# Phase_3.net
KiCad netlist of a schematic drawn in Altium Designer
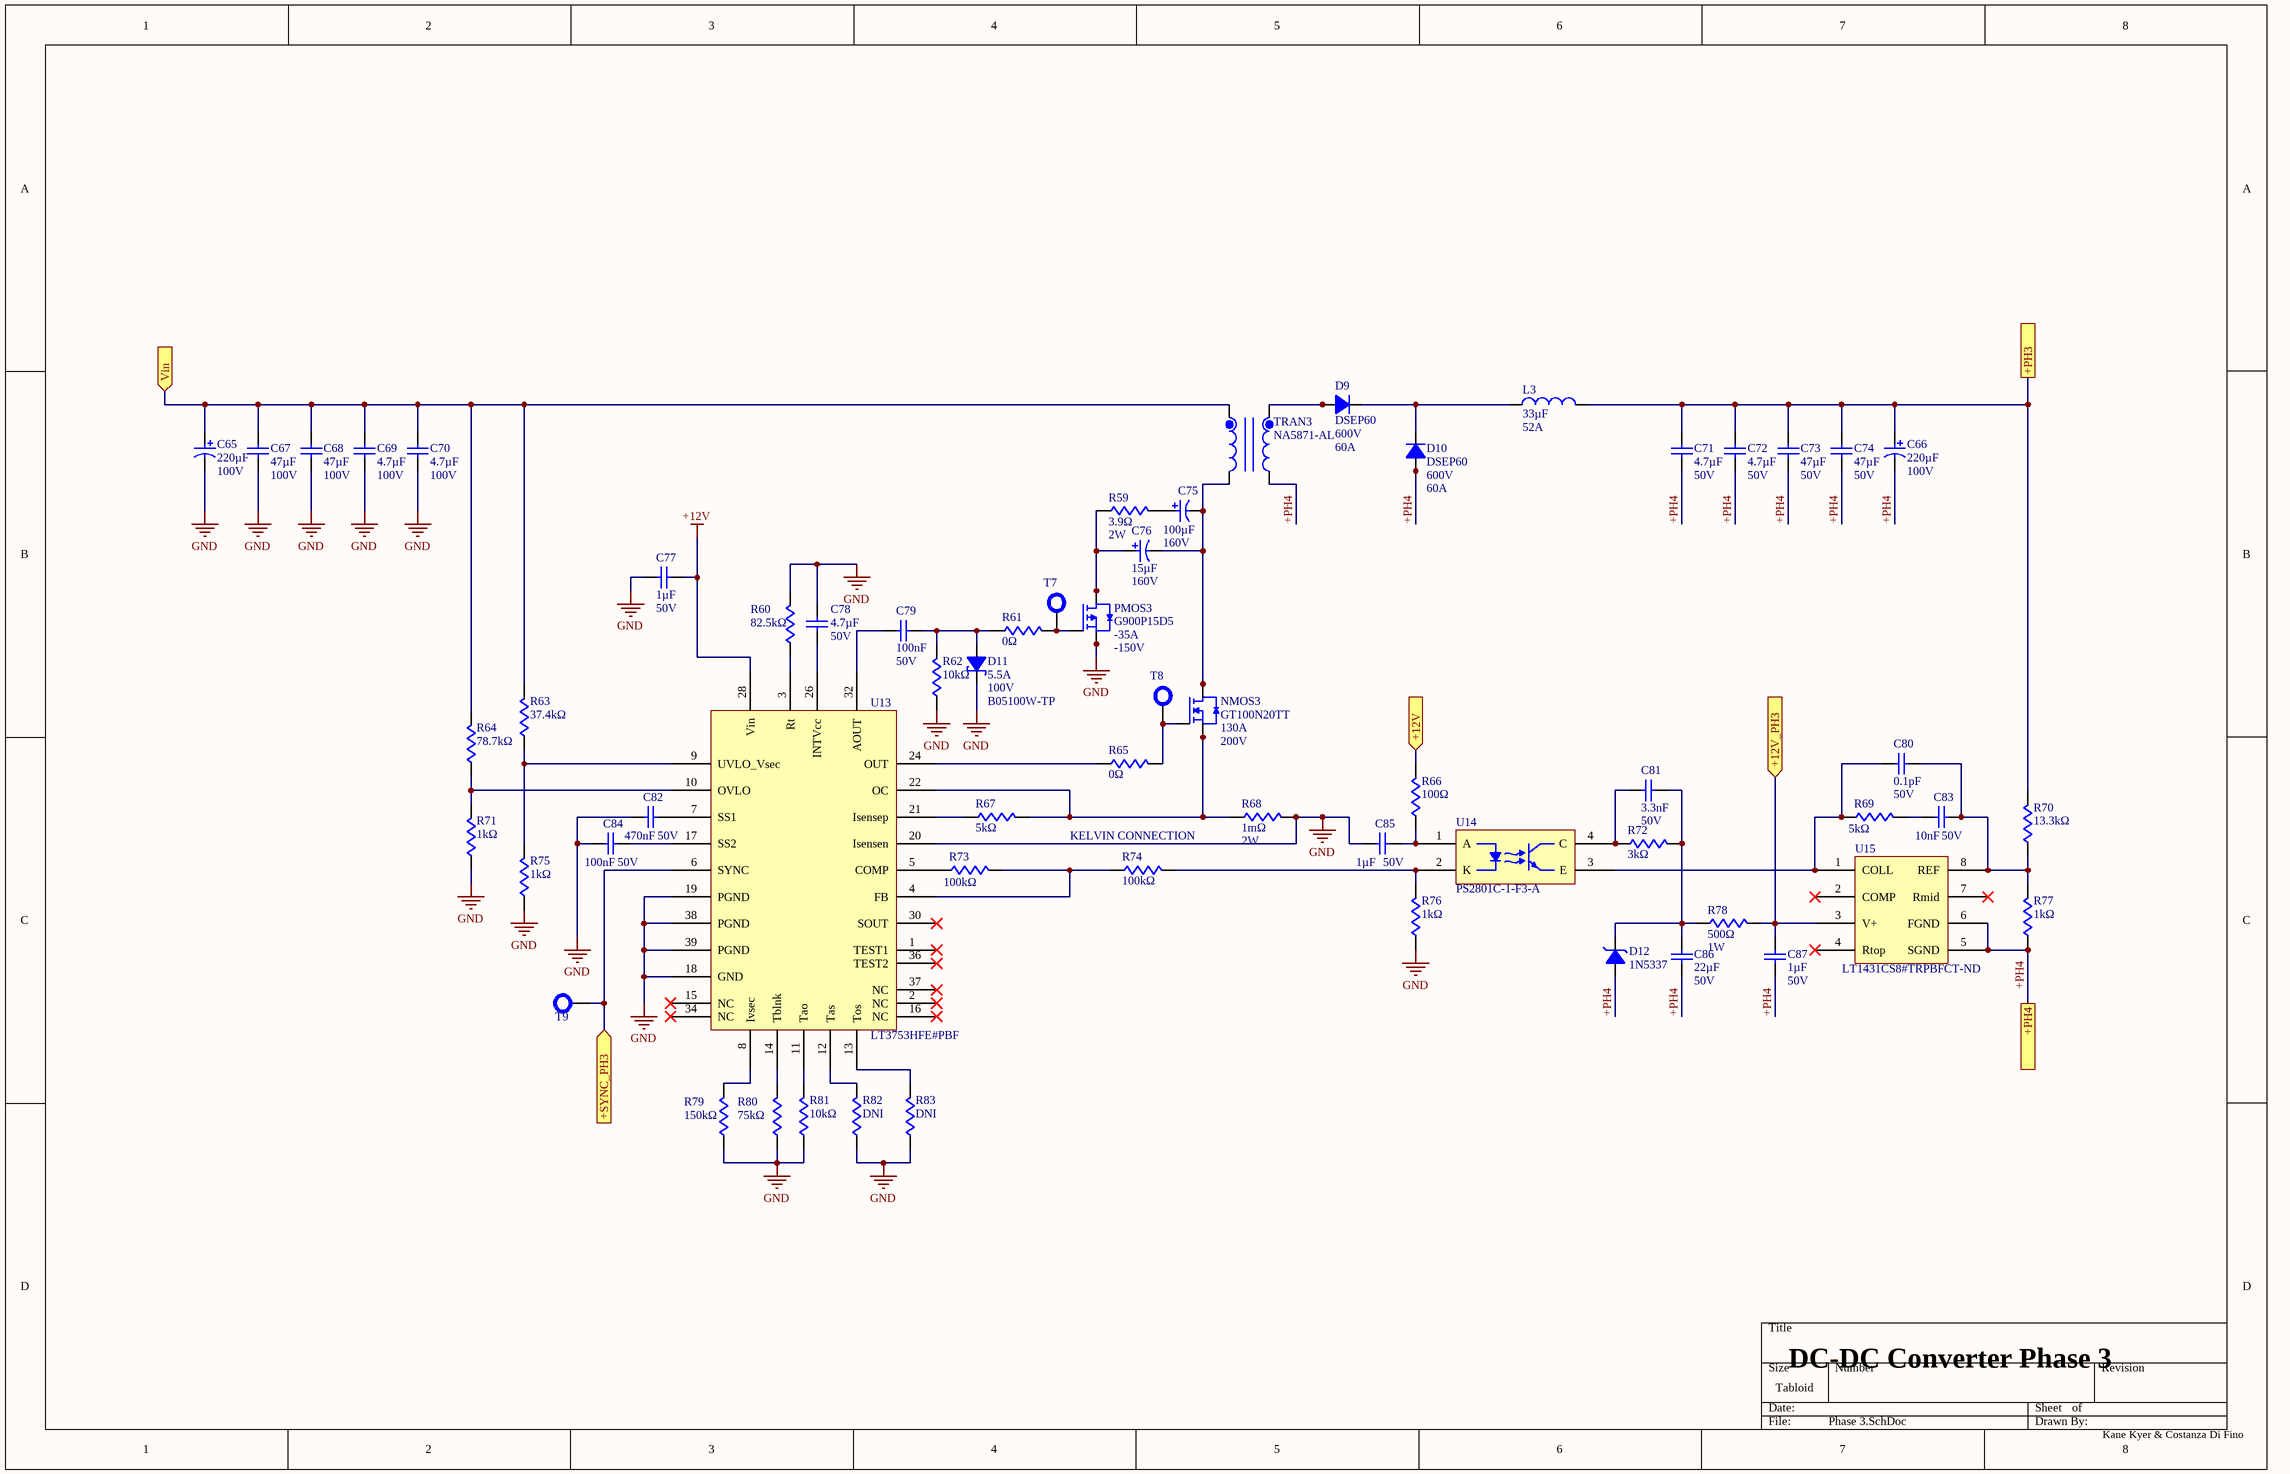
[diagram p0: Phase 3.SchDoc]

(export (version "E")
  (design (tool "Eeschema 10.0.6"))
  (components
    (comp (ref "C65")
      (value "220µF")
      (footprint "C_AEC")
      (description "Radial Can - SMD ALUMINUM ELECTROLYTIC CAPACITOR AFK 100V 220muF ±20% 0.709Dia 18.00mm")
      (fields
        (field (name "MANUFACTURER") "Cornell Dubilier")
        (field (name "MANUFACTURER PART NUMBER") "AFK227M2AR44T-F")
        (field (name "VOLTAGE RATING") "100V")
      )
      (libsource (lib "library") (part "AFK227M2AR44T-F"))
    )
    (comp (ref "C66")
      (value "220µF")
      (footprint "C_AEC")
      (description "Radial Can - SMD ALUMINUM ELECTROLYTIC CAPACITOR AFK 100V 220muF ±20% 0.709Dia 18.00mm")
      (fields
        (field (name "MANUFACTURER") "Cornell Dubilier")
        (field (name "MANUFACTURER PART NUMBER") "AFK227M2AR44T-F")
        (field (name "VOLTAGE RATING") "100V")
      )
      (libsource (lib "library") (part "AFK227M2AR44T-F"))
    )
    (comp (ref "C67")
      (value "47µF")
      (footprint "C_CAA573")
      (description "Multilayer Ceramic Chip Capacitors, Capacitance=47μF, LxWxT: 6.0x7.5x6.4mm")
      (fields
        (field (name "MANUFACTURER") "TDK")
        (field (name "MANUFACTURER PART NUMBER") "CAA573X7S2A476M640LH")
        (field (name "VOLTAGE RATING") "100V")
      )
      (libsource (lib "library") (part "CAA573X7S2A476M640LH"))
    )
    (comp (ref "C68")
      (value "47µF")
      (footprint "C_CAA573")
      (description "Multilayer Ceramic Chip Capacitors, Capacitance=47μF, LxWxT: 6.0x7.5x6.4mm")
      (fields
        (field (name "MANUFACTURER") "TDK")
        (field (name "MANUFACTURER PART NUMBER") "CAA573X7S2A476M640LH")
        (field (name "VOLTAGE RATING") "100V")
      )
      (libsource (lib "library") (part "CAA573X7S2A476M640LH"))
    )
    (comp (ref "C69")
      (value "4.7µF")
      (footprint "C_1210")
      (fields
        (field (name "MANUFACTURER") "Cal-Chip Electronics")
        (field (name "MANUFACTURER PART NUMBER") "GMC32X7S475K100NT")
        (field (name "VOLTAGE RATING (DC)") "100V")
      )
      (libsource (lib "library") (part "GMC32X7S475K100NT"))
    )
    (comp (ref "C70")
      (value "4.7µF")
      (footprint "C_1210")
      (fields
        (field (name "MANUFACTURER") "Cal-Chip Electronics")
        (field (name "MANUFACTURER PART NUMBER") "GMC32X7S475K100NT")
        (field (name "VOLTAGE RATING (DC)") "100V")
      )
      (libsource (lib "library") (part "GMC32X7S475K100NT"))
    )
    (comp (ref "C71")
      (value "4.7µF")
      (footprint "C_1206")
      (fields
        (field (name "MANUFACTURER") "Cal-Chip Electronics")
        (field (name "MANUFACTURER PART NUMBER") "GMC31X7R475K50NT")
        (field (name "VOLTAGE RATING (DC)") "50V")
      )
      (libsource (lib "library") (part "GMC31X7R475K50NT"))
    )
    (comp (ref "C72")
      (value "4.7µF")
      (footprint "C_1206")
      (fields
        (field (name "MANUFACTURER") "Cal-Chip Electronics")
        (field (name "MANUFACTURER PART NUMBER") "GMC31X7R475K50NT")
        (field (name "VOLTAGE RATING (DC)") "50V")
      )
      (libsource (lib "library") (part "GMC31X7R475K50NT"))
    )
    (comp (ref "C73")
      (value "47µF")
      (footprint "C_CKG57N")
      (fields
        (field (name "MANUFACTURER") "TDK")
        (field (name "MANUFACTURER PART NUMBER") "CKG57NX7R1H476M500JJ")
        (field (name "VOLTAGE RATING (DC)") "50V")
      )
      (libsource (lib "library") (part "CKG57NX7R1H476M500JJ"))
    )
    (comp (ref "C74")
      (value "47µF")
      (footprint "C_CKG57N")
      (fields
        (field (name "MANUFACTURER") "TDK")
        (field (name "MANUFACTURER PART NUMBER") "CKG57NX7R1H476M500JJ")
        (field (name "VOLTAGE RATING (DC)") "50V")
      )
      (libsource (lib "library") (part "CKG57NX7R1H476M500JJ"))
    )
    (comp (ref "C75")
      (value "100µF")
      (footprint "UUJ2C101MNJ1MS")
      (description "Aluminum Electrolytic Capacitors 100 F 160 V Radial, SMD 5000 Hrs 105C")
      (fields
        (field (name "MANUFACTURER") "Nichicon")
        (field (name "MANUFACTURER PART NUMBER") "UUJ2C101MNJ1MS")
        (field (name "VOLTAGE RATING (DC)") "160V")
      )
      (libsource (lib "library") (part "UUJ2C101MNJ1MS"))
    )
    (comp (ref "C76")
      (value "15µF")
      (footprint "ULT2C150MNL1GS")
      (description "Radial Can - SMD ALUMINUM ELECTROLYTIC CAPACITOR ULT 160V 15muF ±20% 0.315Dia 8.00mm")
      (fields
        (field (name "MANUFACTURER") "Nichicon")
        (field (name "MANUFACTURER PART NUMBER") "ULT2C150MNL1GS")
        (field (name "VOLTAGE") "160V")
      )
      (libsource (lib "library") (part "ULT2C150MNL1GS"))
    )
    (comp (ref "C77")
      (value "1µF")
      (footprint "C_0805")
      (description "50V 1uF X7R ±10% 0805 Multilayer Ceramic Capacitors MLCC - SMD/SMT ROHS")
      (fields
        (field (name "MANUFACTURER") "Samsung Electro-Mechanics")
        (field (name "MANUFACTURER PART NUMBER") "CL21B105KBFNNNE")
        (field (name "VOLTAGE") "50V")
      )
      (libsource (lib "library") (part "CL21B105KBFNNNE"))
    )
    (comp (ref "C78")
      (value "4.7µF")
      (footprint "C_1206")
      (fields
        (field (name "MANUFACTURER") "Cal-Chip Electronics")
        (field (name "MANUFACTURER PART NUMBER") "GMC31X7R475K50NT")
        (field (name "VOLTAGE RATING (DC)") "50V")
      )
      (libsource (lib "library") (part "GMC31X7R475K50NT"))
    )
    (comp (ref "C79")
      (value "100nF")
      (footprint "C_0603")
      (description "50V 100nF X7R ±10% 0603 Multilayer Ceramic Capacitors MLCC - SMD/SMT ROHS")
      (fields
        (field (name "MANUFACTURER") "KEMET")
        (field (name "MANUFACTURER PART NUMBER") "C0603C104K5RACTU")
        (field (name "VOLTAGE RATING") "50V")
      )
      (libsource (lib "library") (part "C0603C104K5RACTU"))
    )
    (comp (ref "C80")
      (value "0.1pF")
      (footprint "C_0402")
      (description "Multilayer Ceramic Capacitor, 0.1 pF, 50 V, ± 0.05pF, C0G (NP0), 0402 [1005 Metric]")
      (fields
        (field (name "MANUFACTURER") "Murata")
        (field (name "MANUFACTURER PART NUMBER") "GJM1555C1HR10WB01D")
        (field (name "VOLTAGE RATING") "50V")
      )
      (libsource (lib "library") (part "GJM1555C1HR10WB01D"))
    )
    (comp (ref "C81")
      (value "3.3nF")
      (footprint "C_0603")
      (description "50V 3.3nF C0G ±1% 0603 Multilayer Ceramic Capacitors MLCC - SMD/SMT ROHS")
      (fields
        (field (name "MANUFACTURER") "Murata")
        (field (name "MANUFACTURER PART NUMBER") "GCM1885C1H332FA16D")
        (field (name "VOLTAGE RATING") "50V")
      )
      (libsource (lib "library") (part "GCM1885C1H332FA16D"))
    )
    (comp (ref "C82")
      (value "470nF")
      (footprint "C_0402")
      (description "50V 470nF X5R ±10% 0402 Multilayer Ceramic Capacitors MLCC - SMD/SMT ROHS")
      (fields
        (field (name "MANUFACTURER") "Murata")
        (field (name "MANUFACTURER PART NUMBER") "GRM155R61H474KE11D")
        (field (name "VOLTAGE RATING") "50V")
      )
      (libsource (lib "library") (part "GRM155R61H474KE11D"))
    )
    (comp (ref "C83")
      (value "10nF")
      (footprint "C_0603")
      (description "Capacitor, Multilayer, Ceramic, 50V, 10%, X7R, 15% Tc, 0.01Uf, Surface Mount, 0603")
      (fields
        (field (name "MANUFACTURER") "KEMET")
        (field (name "MANUFACTURER PART NUMBER") "C0603C103K5RACTU")
        (field (name "VOLTAGE RATING") "50V")
      )
      (libsource (lib "library") (part "C0603C103K5RACTU"))
    )
    (comp (ref "C84")
      (value "100nF")
      (footprint "C_0603")
      (description "50V 100nF X7R ±10% 0603 Multilayer Ceramic Capacitors MLCC - SMD/SMT ROHS")
      (fields
        (field (name "MANUFACTURER") "KEMET")
        (field (name "MANUFACTURER PART NUMBER") "C0603C104K5RACTU")
        (field (name "VOLTAGE RATING") "50V")
      )
      (libsource (lib "library") (part "C0603C104K5RACTU"))
    )
    (comp (ref "C85")
      (value "1µF")
      (footprint "C_0805")
      (description "50V 1uF X7R ±10% 0805 Multilayer Ceramic Capacitors MLCC - SMD/SMT ROHS")
      (fields
        (field (name "MANUFACTURER") "Samsung Electro-Mechanics")
        (field (name "MANUFACTURER PART NUMBER") "CL21B105KBFNNNE")
        (field (name "VOLTAGE") "50V")
      )
      (libsource (lib "library") (part "CL21B105KBFNNNE"))
    )
    (comp (ref "C86")
      (value "22µF")
      (footprint "C_2220")
      (fields
        (field (name "MANUFACTURER") "Cal-Chip Electronics")
        (field (name "MANUFACTURER PART NUMBER") "GMC55X7R226M50NT")
        (field (name "VOLTAGE RATING (DC)") "50V")
      )
      (libsource (lib "library") (part "GMC55X7R226M50NT"))
    )
    (comp (ref "C87")
      (value "1µF")
      (footprint "C_0805")
      (description "50V 1uF X7R ±10% 0805 Multilayer Ceramic Capacitors MLCC - SMD/SMT ROHS")
      (fields
        (field (name "MANUFACTURER") "Samsung Electro-Mechanics")
        (field (name "MANUFACTURER PART NUMBER") "CL21B105KBFNNNE")
        (field (name "VOLTAGE") "50V")
      )
      (libsource (lib "library") (part "CL21B105KBFNNNE"))
    )
    (comp (ref "D9")
      (value "DSEP60")
      (footprint "D_DSEP60")
      (description "Power Diode Discretes-FRED TO-")
      (fields
        (field (name "MANUFACTURER") "IXYS")
        (field (name "MANUFACTURER PART NUMBER") "DSEP60-06AZ-TRL")
        (field (name "VR") "600V")
        (field (name "IO") "60A")
      )
      (libsource (lib "library") (part "DSEP60-06AZ-TRL"))
    )
    (comp (ref "D10")
      (value "DSEP60")
      (footprint "D_DSEP60")
      (description "Power Diode Discretes-FRED TO-")
      (fields
        (field (name "MANUFACTURER") "IXYS")
        (field (name "MANUFACTURER PART NUMBER") "DSEP60-06AZ-TRL")
        (field (name "VR") "600V")
        (field (name "IO") "60A")
      )
      (libsource (lib "library") (part "DSEP60-06AZ-TRL"))
    )
    (comp (ref "D11")
      (value "B05100W-TP")
      (footprint "D_B05100W")
      (description "Rectifier Diode, Schottky, 1 Phase, 1 Element, 0.5A, 100V V(RRM), Silicon")
      (fields
        (field (name "MANUFACTURER") "MCC")
        (field (name "MAX FORWARD SURGE CURRENT (IFSM)") "5.5A")
        (field (name "MIN BREAKDOWN VOLTAGE") "100V")
        (field (name "MANUFACTURER PART NUMBER") "B05100W-TP")
      )
      (libsource (lib "library") (part "B05100W-TP"))
    )
    (comp (ref "D12")
      (value "1N5337BRLG")
      (footprint "D_1N5337")
      (description "Zener Diode Single 4.7V 5% 2Ohm 5000mW 2-Pin Case 017AA-01 T/R / DIODE ZENER 4.7V 5W AXIAL")
      (fields
        (field (name "MANUFACTURER") "onsemi")
        (field (name "TOLERANCE") "5%")
        (field (name "SUPPLIER PART NUMBER") "1N5337")
      )
      (libsource (lib "library") (part "1N5337BRLG"))
    )
    (comp (ref "L3")
      (value "33µF")
      (footprint "CPEX4141L-330MC")
      (description "Fixed Ind 33UH 52A 1.88 Mohm Th")
      (fields
        (field (name "MANUFACTURER") "Codaca")
        (field (name "MANUFACTURER PART NUMBER") "CPEX4141L-330MC")
        (field (name "IRMS") "52A")
      )
      (libsource (lib "library") (part "CPEX4141L-330MC"))
    )
    (comp (ref "NMOS3")
      (value "GT100N20TT")
      (footprint "GT100N20TT")
      (description "Mosfet N-ch 200V 130A 280W Tolt")
      (fields
        (field (name "MANUFACTURER") "GoFord")
        (field (name "MANUFACTURER PART NUMBER") "GT100N20TT")
        (field (name "ID") "130A")
        (field (name "VDS") "200V")
      )
      (libsource (lib "library") (part "GT100N20TT"))
    )
    (comp (ref "PMOS3")
      (value "G900P15D5")
      (footprint "G900P15")
      (description "P-150V, -60A, RD(max) Less Than 80mOhm at -10V, VTH -1V to -4V, DFN5x6-8L")
      (fields
        (field (name "MANUFACTURER") "GoFord")
        (field (name "MANUFACTURER PART NUMBER") "G900P15D5")
        (field (name "ID") "-35A")
        (field (name "VDS") "-150V")
      )
      (libsource (lib "library") (part "G900P15D5"))
    )
    (comp (ref "R59")
      (value "3.9Ω")
      (footprint "R_SM2W")
      (description "SM Series 3.9 Ohm ±5 % 2 W ±200 ppm/°C Surface Mount Wirewound Resistor")
      (fields
        (field (name "MANUFACTURER") "TE Connectivity")
        (field (name "MANUFACTURER PART NUMBER") "SMW23R9JT")
        (field (name "POWER RATING") "2W")
      )
      (libsource (lib "library") (part "SMW23R9JT"))
    )
    (comp (ref "R60")
      (value "82.5kΩ")
      (footprint "R_0805")
      (description "Res Thick Film 0805 82.5K Ohm 1% 1/8W ±100ppm/°C Molded SMD SMD Paper T/R")
      (fields
        (field (name "MANUFACTURER") "Stackpole Electronics")
        (field (name "MANUFACTURER PART NUMBER") "RMCF0805FT82K5")
      )
      (libsource (lib "library") (part "RMCF0805FT82K5"))
    )
    (comp (ref "R61")
      (value "0Ω")
      (footprint "R_0805")
      (description "Zero Ohm Resistor, Jumper, 0805 [2012 Metric], Thick Film, 125 mW, 2.5 A, Surface Mount Device")
      (fields
        (field (name "MANUFACTURER") "Vishay")
        (field (name "MANUFACTURER PART NUMBER") "CRCW08050000Z0EA")
      )
      (libsource (lib "library") (part "CRCW08050000Z0EA"))
    )
    (comp (ref "R62")
      (value "10kΩ")
      (footprint "R_0402")
      (description "Fixed Resistor, Metal Glaze/thick Film, 0.0625W, 10000ohm, 50V, 1% +/-Tol, Surface Mount, 0402")
      (fields
        (field (name "MANUFACTURER") "Cal-Chip Electronics")
        (field (name "MANUFACTURER PART NUMBER") "RM04F1002CT")
      )
      (libsource (lib "library") (part "RM04F1002CT"))
    )
    (comp (ref "R63")
      (value "37.4kΩ")
      (footprint "R_0603")
      (description "100mW Thick Film Resistors 75V ±100ppm/℃ ±1% 37.4kΩ 0603 Chip Resistor - Surface Mount ROHS")
      (fields
        (field (name "MANUFACTURER") "Yageo Group")
        (field (name "MANUFACTURER PART NUMBER") "RC0603FR-0737K4L")
      )
      (libsource (lib "library") (part "RC0603FR-0737K4L"))
    )
    (comp (ref "R64")
      (value "78.7kΩ")
      (footprint "R_0603")
      (description "Res Thick Film 0603 78.7K Ohm 1% 0.1W(1/10W) ±100ppm/C Pad SMD T/R")
      (fields
        (field (name "MANUFACTURER") "Yageo Group")
        (field (name "MANUFACTURER PART NUMBER") "RC0603FR-0778K7L")
      )
      (libsource (lib "library") (part "RC0603FR-0778K7L"))
    )
    (comp (ref "R65")
      (value "0Ω")
      (footprint "R_0805")
      (description "Zero Ohm Resistor, Jumper, 0805 [2012 Metric], Thick Film, 125 mW, 2.5 A, Surface Mount Device")
      (fields
        (field (name "MANUFACTURER") "Vishay")
        (field (name "MANUFACTURER PART NUMBER") "CRCW08050000Z0EA")
      )
      (libsource (lib "library") (part "CRCW08050000Z0EA"))
    )
    (comp (ref "R66")
      (value "100Ω")
      (footprint "R_0603")
      (description "Yageo RC0603FR-07100RL 0603 SMD Resistor 100 Ohm thin film chip resistor")
      (fields
        (field (name "MANUFACTURER") "Yageo Group")
        (field (name "MANUFACTURER PART NUMBER") "RC0603FR-07100RL")
      )
      (libsource (lib "library") (part "RC0603FR-07100RL"))
    )
    (comp (ref "R67")
      (value "5kΩ")
      (footprint "R_0402")
      (description "Res Thin Film 0402 5K Ohm 0.1% 0.05W(1/20W) +/-25ppm/C Sulfur Resistant Pad SMD Medical T/R")
      (fields
        (field (name "MANUFACTURER") "Vishay")
        (field (name "MANUFACTURER PART NUMBER") "PNM0402E5001BST1")
      )
      (libsource (lib "library") (part "PNM0402E5001BST1"))
    )
    (comp (ref "R68")
      (value "1mΩ")
      (footprint "R_2512")
      (description "Res Thick Film 2512 1m Ohm 1% 2W ±75ppm/°C Molded SMD Embossed T/R")
      (fields
        (field (name "MANUFACTURER") "Bourns")
        (field (name "MANUFACTURER PART NUMBER") "CRE2512-FZ-R001E-2")
        (field (name "POWER RATING") "2W")
      )
      (libsource (lib "library") (part "CRE2512-FZ-R001E-2"))
    )
    (comp (ref "R69")
      (value "5kΩ")
      (footprint "R_0402")
      (description "Res Thin Film 0402 5K Ohm 0.1% 0.05W(1/20W) +/-25ppm/C Sulfur Resistant Pad SMD Medical T/R")
      (fields
        (field (name "MANUFACTURER") "Vishay")
        (field (name "MANUFACTURER PART NUMBER") "PNM0402E5001BST1")
      )
      (libsource (lib "library") (part "PNM0402E5001BST1"))
    )
    (comp (ref "R70")
      (value "13.3kΩ")
      (footprint "R_0603")
      (description "Res Thick Film 0603 13.3K Ohm 1% 0.1W(1/10W) ±100ppm/C Pad SMD Automotive T/R")
      (fields
        (field (name "MANUFACTURER") "Stackpole Electronics")
        (field (name "MANUFACTURER PART NUMBER") "RMCF0603FT13K3")
      )
      (libsource (lib "library") (part "RMCF0603FT13K3"))
    )
    (comp (ref "R71")
      (value "1kΩ")
      (footprint "R_0402")
      (description "62.5mW Thick Film Resistors ±100ppm/℃ ±1% 1kΩ 0402 Chip Resistor - Surface Mount ROHS")
      (fields
        (field (name "MANUFACTURER") "Cal-Chip Electronics")
        (field (name "MANUFACTURER PART NUMBER") "RM04F1001CT")
      )
      (libsource (lib "library") (part "RM04F1001CT"))
    )
    (comp (ref "R72")
      (value "3kΩ")
      (footprint "C_0402")
      (description "Res Thick Film 0402 3K Ohm 1% 0.063W(1/16W) ±100ppm/C Pad SMD Automotive T/R")
      (fields
        (field (name "MANUFACTURER") "Yageo Group")
        (field (name "MANUFACTURER PART NUMBER") "AC0402FR-073KL")
      )
      (libsource (lib "library") (part "AC0402FR-073KL"))
    )
    (comp (ref "R73")
      (value "100kΩ")
      (footprint "R_0402")
      (description "Fixed Resistor, Metal Glaze/thick Film, 0.0625W, 100000ohm, 50V, 1% +/-Tol, Surface Mount, 0402")
      (fields
        (field (name "MANUFACTURER") "Cal-Chip Electronics")
        (field (name "MANUFACTURER PART NUMBER") "RM04F1003CT")
      )
      (libsource (lib "library") (part "RM04F1003CT"))
    )
    (comp (ref "R74")
      (value "100kΩ")
      (footprint "R_0402")
      (description "Fixed Resistor, Metal Glaze/thick Film, 0.0625W, 100000ohm, 50V, 1% +/-Tol, Surface Mount, 0402")
      (fields
        (field (name "MANUFACTURER") "Cal-Chip Electronics")
        (field (name "MANUFACTURER PART NUMBER") "RM04F1003CT")
      )
      (libsource (lib "library") (part "RM04F1003CT"))
    )
    (comp (ref "R75")
      (value "1kΩ")
      (footprint "R_0402")
      (description "62.5mW Thick Film Resistors ±100ppm/℃ ±1% 1kΩ 0402 Chip Resistor - Surface Mount ROHS")
      (fields
        (field (name "MANUFACTURER") "Cal-Chip Electronics")
        (field (name "MANUFACTURER PART NUMBER") "RM04F1001CT")
      )
      (libsource (lib "library") (part "RM04F1001CT"))
    )
    (comp (ref "R76")
      (value "1kΩ")
      (footprint "R_0402")
      (description "62.5mW Thick Film Resistors ±100ppm/℃ ±1% 1kΩ 0402 Chip Resistor - Surface Mount ROHS")
      (fields
        (field (name "MANUFACTURER") "Cal-Chip Electronics")
        (field (name "MANUFACTURER PART NUMBER") "RM04F1001CT")
      )
      (libsource (lib "library") (part "RM04F1001CT"))
    )
    (comp (ref "R77")
      (value "1kΩ")
      (footprint "R_0402")
      (description "62.5mW Thick Film Resistors ±100ppm/℃ ±1% 1kΩ 0402 Chip Resistor - Surface Mount ROHS")
      (fields
        (field (name "MANUFACTURER") "Cal-Chip Electronics")
        (field (name "MANUFACTURER PART NUMBER") "RM04F1001CT")
      )
      (libsource (lib "library") (part "RM04F1001CT"))
    )
    (comp (ref "R78")
      (value "500Ω")
      (footprint "R_WSC2515")
      (description "Fixed Resistor, Wire Wound, 1W, 500ohm, 22.3607V, 1% +/-Tol, 20ppm/Cel, Surface Mount, 2515")
      (fields
        (field (name "MANUFACTURER") "Vishay")
        (field (name "MANUFACTURER PART NUMBER") "WSC2515500R0FEB")
        (field (name "POWER RATING") "1W")
      )
      (libsource (lib "library") (part "WSC2515500R0FEB"))
    )
    (comp (ref "R79")
      (value "150kΩ")
      (footprint "R_0603")
      (description "100mW Thick Film Resistors 75V ±100ppm/℃ ±1% 150kΩ 0603 Chip Resistor - Surface Mount ROHS")
      (fields
        (field (name "MANUFACTURER") "Yageo Group")
        (field (name "MANUFACTURER PART NUMBER") "RC0603FR-07150KL")
      )
      (libsource (lib "library") (part "RC0603FR-07150KL"))
    )
    (comp (ref "R80")
      (value "75kΩ")
      (footprint "R_0603")
      (description "Res Thick Film 0603 75K Ohm 1% 0.1W(1/10W) ±100ppm/C Pad SMD T/R Automotive AEC-Q200")
      (fields
        (field (name "MANUFACTURER") "Yageo Group")
        (field (name "MANUFACTURER PART NUMBER") "AC0603FR-0775KL")
      )
      (libsource (lib "library") (part "AC0603FR-0775KL"))
    )
    (comp (ref "R81")
      (value "10kΩ")
      (footprint "R_0402")
      (description "Fixed Resistor, Metal Glaze/thick Film, 0.0625W, 10000ohm, 50V, 1% +/-Tol, Surface Mount, 0402")
      (fields
        (field (name "MANUFACTURER") "Cal-Chip Electronics")
        (field (name "MANUFACTURER PART NUMBER") "RM04F1002CT")
      )
      (libsource (lib "library") (part "RM04F1002CT"))
    )
    (comp (ref "R82")
      (value "DNI")
      (footprint "R_0805")
      (description "Zero Ohm Resistor, Jumper, 0805 [2012 Metric], Thick Film, 125 mW, 2.5 A, Surface Mount Device")
      (fields
        (field (name "MANUFACTURER") "Vishay")
        (field (name "MANUFACTURER PART NUMBER") "CRCW08050000Z0EA")
      )
      (libsource (lib "library") (part "CRCW08050000Z0EA"))
    )
    (comp (ref "R83")
      (value "DNI")
      (footprint "R_0805")
      (description "Zero Ohm Resistor, Jumper, 0805 [2012 Metric], Thick Film, 125 mW, 2.5 A, Surface Mount Device")
      (fields
        (field (name "MANUFACTURER") "Vishay")
        (field (name "MANUFACTURER PART NUMBER") "CRCW08050000Z0EA")
      )
      (libsource (lib "library") (part "CRCW08050000Z0EA"))
    )
    (comp (ref "T7") (value "TEST") (footprint "TEST_POINT") (libsource (lib "library") (part "TEST")))
    (comp (ref "T8") (value "TEST") (footprint "TEST_POINT") (libsource (lib "library") (part "TEST")))
    (comp (ref "T9") (value "TEST") (footprint "TEST_POINT") (libsource (lib "library") (part "TEST")))
    (comp (ref "TRAN3")
      (value "NA5871-AL")
      (footprint "NA5871-AL")
      (description "Transformer, planar, for TI UCC28950, SMT, RoHS")
      (fields (field (name "MANUFACTURER") "Coilcraft") (field (name "SUPPLIER PART NUMBER") "NA5871-AL"))
      (libsource (lib "library") (part "NA5871-AL"))
    )
    (comp (ref "U13")
      (value "LT3753HFE#PBF")
      (footprint "LT3753")
      (description "500kHz 8.5V~100V Buck-boost type 1 TSSOP-38-EP-4.4mm DC-DC Controllers ROHS")
      (fields
        (field (name "MANUFACTURER") "Analog Devices")
        (field (name "MANUFACTURER PART NUMBER") "LT3753HFE#PBF")
      )
      (libsource (lib "library") (part "LT3753HFE#PBF"))
    )
    (comp (ref "U14")
      (value "PS2801C-1-F3-A")
      (footprint "PS2801C")
      (description "Optocoupler DC-IN 1-CH Transistor DC-OUT 4-Pin SSOP T/R")
      (fields
        (field (name "MANUFACTURER") "Renesas")
        (field (name "MANUFACTURER PART NUMBER") "PS2801C-1-F3-A")
      )
      (libsource (lib "library") (part "PS2801C-1-F3-A"))
    )
    (comp (ref "U15")
      (value "LT1431CS8#TRPBF")
      (footprint "LT1431")
      (description "V-Ref Adjustable 2.5V to 36V 100mA 8-Pin SOIC N T/R")
      (fields
        (field (name "SUPPLIER PART NUMBER") "LT1431CS8#TRPBFCT-ND")
        (field (name "MANUFACTURER") "Analog Devices")
        (field (name "TOLERANCE") "0.4%")
      )
      (libsource (lib "library") (part "LT1431CS8#TRPBF"))
    )
  )
  (nets
    (net (code "1") (name "+12V") (class "Default")
      (node (ref "C77") (pin "2") (pintype "passive"))
      (node (ref "R66") (pin "2") (pintype "passive"))
      (node (ref "U13") (pin "28") (pinfunction "Vin_28") (pintype "passive"))
    )
    (net (code "2") (name "/+12V_PH3") (class "Default")
      (node (ref "C87") (pin "2") (pintype "passive"))
      (node (ref "R78") (pin "2") (pintype "passive"))
      (node (ref "U15") (pin "3") (pinfunction "V+_3") (pintype "passive"))
    )
    (net (code "3") (name "/+PH3") (class "Default")
      (node (ref "C66") (pin "1") (pintype "passive"))
      (node (ref "C71") (pin "2") (pintype "passive"))
      (node (ref "C72") (pin "2") (pintype "passive"))
      (node (ref "C73") (pin "2") (pintype "passive"))
      (node (ref "C74") (pin "2") (pintype "passive"))
      (node (ref "L3") (pin "2") (pintype "passive"))
      (node (ref "R70") (pin "2") (pintype "passive"))
    )
    (net (code "4") (name "/+PH4") (class "Default")
      (node (ref "C66") (pin "2") (pintype "passive"))
      (node (ref "C71") (pin "1") (pintype "passive"))
      (node (ref "C72") (pin "1") (pintype "passive"))
      (node (ref "C73") (pin "1") (pintype "passive"))
      (node (ref "C74") (pin "1") (pintype "passive"))
      (node (ref "C86") (pin "1") (pintype "passive"))
      (node (ref "C87") (pin "1") (pintype "passive"))
      (node (ref "D10") (pin "1") (pinfunction "A_1") (pintype "passive"))
      (node (ref "D10") (pin "3") (pinfunction "A_3") (pintype "passive"))
      (node (ref "D12") (pin "2") (pintype "passive"))
      (node (ref "R77") (pin "1") (pintype "passive"))
      (node (ref "TRAN3") (pin "11") (pintype "passive"))
      (node (ref "U15") (pin "5") (pinfunction "SGND_5") (pintype "passive"))
      (node (ref "U15") (pin "6") (pinfunction "FGND_6") (pintype "passive"))
    )
    (net (code "5") (name "/+SYNC_PH3") (class "Default")
      (node (ref "T9") (pin "1") (pinfunction "1_1") (pintype "passive"))
      (node (ref "U13") (pin "6") (pinfunction "SYNC_6") (pintype "passive"))
    )
    (net (code "6") (name "/Vin") (class "Default")
      (node (ref "C65") (pin "1") (pintype "passive"))
      (node (ref "C67") (pin "2") (pintype "passive"))
      (node (ref "C68") (pin "2") (pintype "passive"))
      (node (ref "C69") (pin "2") (pintype "passive"))
      (node (ref "C70") (pin "2") (pintype "passive"))
      (node (ref "R63") (pin "2") (pintype "passive"))
      (node (ref "R64") (pin "2") (pintype "passive"))
      (node (ref "TRAN3") (pin "1") (pintype "passive"))
    )
    (net (code "7") (name "GND") (class "Default")
      (node (ref "C65") (pin "2") (pintype "passive"))
      (node (ref "C67") (pin "1") (pintype "passive"))
      (node (ref "C68") (pin "1") (pintype "passive"))
      (node (ref "C69") (pin "1") (pintype "passive"))
      (node (ref "C70") (pin "1") (pintype "passive"))
      (node (ref "C77") (pin "1") (pintype "passive"))
      (node (ref "C78") (pin "1") (pintype "passive"))
      (node (ref "C82") (pin "1") (pintype "passive"))
      (node (ref "C84") (pin "1") (pintype "passive"))
      (node (ref "C85") (pin "1") (pintype "passive"))
      (node (ref "D11") (pin "1") (pintype "passive"))
      (node (ref "PMOS3") (pin "1") (pinfunction "S_1") (pintype "passive"))
      (node (ref "PMOS3") (pin "2") (pinfunction "S_2") (pintype "passive"))
      (node (ref "PMOS3") (pin "3") (pinfunction "S_3") (pintype "passive"))
      (node (ref "R60") (pin "2") (pintype "passive"))
      (node (ref "R62") (pin "1") (pintype "passive"))
      (node (ref "R68") (pin "2") (pintype "passive"))
      (node (ref "R71") (pin "1") (pintype "passive"))
      (node (ref "R75") (pin "1") (pintype "passive"))
      (node (ref "R76") (pin "1") (pintype "passive"))
      (node (ref "R79") (pin "1") (pintype "passive"))
      (node (ref "R80") (pin "1") (pintype "passive"))
      (node (ref "R81") (pin "1") (pintype "passive"))
      (node (ref "R82") (pin "1") (pintype "passive"))
      (node (ref "R83") (pin "1") (pintype "passive"))
      (node (ref "U13") (pin "18") (pinfunction "GND_18") (pintype "passive"))
      (node (ref "U13") (pin "19") (pinfunction "PGND_19") (pintype "passive"))
      (node (ref "U13") (pin "20") (pinfunction "Isensen_20") (pintype "passive"))
      (node (ref "U13") (pin "38") (pinfunction "PGND_38") (pintype "passive"))
      (node (ref "U13") (pin "39") (pinfunction "PGND_39") (pintype "passive"))
    )
    (net (code "8") (name "Net-(C75-Pad1)") (class "Default")
      (node (ref "C75") (pin "1") (pintype "passive"))
      (node (ref "R59") (pin "2") (pintype "passive"))
    )
    (net (code "9") (name "Net-(C75-Pad2)") (class "Default")
      (node (ref "C75") (pin "2") (pintype "passive"))
      (node (ref "C76") (pin "2") (pintype "passive"))
      (node (ref "NMOS3") (pin "10") (pinfunction "D_10") (pintype "passive"))
      (node (ref "NMOS3") (pin "11") (pinfunction "D_11") (pintype "passive"))
      (node (ref "NMOS3") (pin "12") (pinfunction "D_12") (pintype "passive"))
      (node (ref "NMOS3") (pin "13") (pinfunction "D_13") (pintype "passive"))
      (node (ref "NMOS3") (pin "14") (pinfunction "D_14") (pintype "passive"))
      (node (ref "NMOS3") (pin "15") (pinfunction "D_15") (pintype "passive"))
      (node (ref "NMOS3") (pin "16") (pinfunction "D_16") (pintype "passive"))
      (node (ref "NMOS3") (pin "9") (pinfunction "D_9") (pintype "passive"))
      (node (ref "TRAN3") (pin "4") (pintype "passive"))
    )
    (net (code "10") (name "Net-(C76-Pad1)") (class "Default")
      (node (ref "C76") (pin "1") (pintype "passive"))
      (node (ref "PMOS3") (pin "5") (pinfunction "D_5") (pintype "passive"))
      (node (ref "PMOS3") (pin "6") (pinfunction "D_6") (pintype "passive"))
      (node (ref "PMOS3") (pin "7") (pinfunction "D_7") (pintype "passive"))
      (node (ref "PMOS3") (pin "8") (pinfunction "D_8") (pintype "passive"))
      (node (ref "R59") (pin "1") (pintype "passive"))
    )
    (net (code "11") (name "Net-(C79-Pad2)") (class "Default")
      (node (ref "C79") (pin "2") (pintype "passive"))
      (node (ref "D11") (pin "2") (pintype "passive"))
      (node (ref "R61") (pin "1") (pintype "passive"))
      (node (ref "R62") (pin "2") (pintype "passive"))
    )
    (net (code "12") (name "Net-(C81-Pad2)") (class "Default")
      (node (ref "C81") (pin "2") (pintype "passive"))
      (node (ref "C86") (pin "2") (pintype "passive"))
      (node (ref "D12") (pin "1") (pintype "passive"))
      (node (ref "R72") (pin "2") (pintype "passive"))
      (node (ref "R78") (pin "1") (pintype "passive"))
    )
    (net (code "13") (name "Net-(C83-Pad1)") (class "Default")
      (node (ref "C83") (pin "1") (pintype "passive"))
      (node (ref "R69") (pin "2") (pintype "passive"))
    )
    (net (code "14") (name "Net-(D9-A-Pad1)") (class "Default")
      (node (ref "D9") (pin "1") (pinfunction "A_1") (pintype "passive"))
      (node (ref "D9") (pin "3") (pinfunction "A_3") (pintype "passive"))
      (node (ref "TRAN3") (pin "6") (pintype "passive"))
    )
    (net (code "15") (name "Net-(D10-C)") (class "Default")
      (node (ref "D10") (pin "4") (pinfunction "C_4") (pintype "passive"))
      (node (ref "D9") (pin "4") (pinfunction "C_4") (pintype "passive"))
      (node (ref "L3") (pin "1") (pintype "passive"))
    )
    (net (code "16") (name "Net-(NMOS3-G)") (class "Default")
      (node (ref "NMOS3") (pin "8") (pinfunction "G_8") (pintype "passive"))
      (node (ref "R65") (pin "2") (pintype "passive"))
      (node (ref "T8") (pin "1") (pinfunction "1_1") (pintype "passive"))
    )
    (net (code "17") (name "Net-(PMOS3-G)") (class "Default")
      (node (ref "PMOS3") (pin "4") (pinfunction "G_4") (pintype "passive"))
      (node (ref "R61") (pin "2") (pintype "passive"))
      (node (ref "T7") (pin "1") (pinfunction "1_1") (pintype "passive"))
    )
    (net (code "18") (name "Net-(U13-AOUT)") (class "Default")
      (node (ref "C79") (pin "1") (pintype "passive"))
      (node (ref "U13") (pin "32") (pinfunction "AOUT_32") (pintype "passive"))
    )
    (net (code "19") (name "Net-(U13-COMP)") (class "Default")
      (node (ref "R73") (pin "1") (pintype "passive"))
      (node (ref "U13") (pin "5") (pinfunction "COMP_5") (pintype "passive"))
    )
    (net (code "20") (name "Net-(U13-FB)") (class "Default")
      (node (ref "R73") (pin "2") (pintype "passive"))
      (node (ref "R74") (pin "1") (pintype "passive"))
      (node (ref "U13") (pin "4") (pinfunction "FB_4") (pintype "passive"))
    )
    (net (code "21") (name "Net-(U13-INTVcc)") (class "Default")
      (node (ref "C78") (pin "2") (pintype "passive"))
      (node (ref "U13") (pin "26") (pinfunction "INTVcc_26") (pintype "passive"))
    )
    (net (code "22") (name "Net-(U13-Isensep)") (class "Default")
      (node (ref "R67") (pin "1") (pintype "passive"))
      (node (ref "U13") (pin "21") (pinfunction "Isensep_21") (pintype "passive"))
    )
    (net (code "23") (name "Net-(U13-Ivsec)") (class "Default")
      (node (ref "R79") (pin "2") (pintype "passive"))
      (node (ref "U13") (pin "8") (pinfunction "Ivsec_8") (pintype "passive"))
    )
    (net (code "24") (name "Net-(U13-OC)") (class "Default")
      (node (ref "NMOS3") (pin "1") (pinfunction "S_1") (pintype "passive"))
      (node (ref "NMOS3") (pin "2") (pinfunction "S_2") (pintype "passive"))
      (node (ref "NMOS3") (pin "3") (pinfunction "S_3") (pintype "passive"))
      (node (ref "NMOS3") (pin "4") (pinfunction "S_4") (pintype "passive"))
      (node (ref "NMOS3") (pin "5") (pinfunction "S_5") (pintype "passive"))
      (node (ref "NMOS3") (pin "6") (pinfunction "S_6") (pintype "passive"))
      (node (ref "NMOS3") (pin "7") (pinfunction "S_7") (pintype "passive"))
      (node (ref "R67") (pin "2") (pintype "passive"))
      (node (ref "R68") (pin "1") (pintype "passive"))
      (node (ref "U13") (pin "22") (pinfunction "OC_22") (pintype "passive"))
    )
    (net (code "25") (name "Net-(U13-OUT)") (class "Default")
      (node (ref "R65") (pin "1") (pintype "passive"))
      (node (ref "U13") (pin "24") (pinfunction "OUT_24") (pintype "passive"))
    )
    (net (code "26") (name "Net-(U13-OVLO)") (class "Default")
      (node (ref "R64") (pin "1") (pintype "passive"))
      (node (ref "R71") (pin "2") (pintype "passive"))
      (node (ref "U13") (pin "10") (pinfunction "OVLO_10") (pintype "passive"))
    )
    (net (code "27") (name "Net-(U13-Rt)") (class "Default")
      (node (ref "R60") (pin "1") (pintype "passive"))
      (node (ref "U13") (pin "3") (pinfunction "Rt_3") (pintype "passive"))
    )
    (net (code "28") (name "Net-(U13-SS1)") (class "Default")
      (node (ref "C82") (pin "2") (pintype "passive"))
      (node (ref "U13") (pin "7") (pinfunction "SS1_7") (pintype "passive"))
    )
    (net (code "29") (name "Net-(U13-SS2)") (class "Default")
      (node (ref "C84") (pin "2") (pintype "passive"))
      (node (ref "U13") (pin "17") (pinfunction "SS2_17") (pintype "passive"))
    )
    (net (code "30") (name "Net-(U13-Tao)") (class "Default")
      (node (ref "R81") (pin "2") (pintype "passive"))
      (node (ref "U13") (pin "11") (pinfunction "Tao_11") (pintype "passive"))
    )
    (net (code "31") (name "Net-(U13-Tas)") (class "Default")
      (node (ref "R82") (pin "2") (pintype "passive"))
      (node (ref "U13") (pin "12") (pinfunction "Tas_12") (pintype "passive"))
    )
    (net (code "32") (name "Net-(U13-Tblnk)") (class "Default")
      (node (ref "R80") (pin "2") (pintype "passive"))
      (node (ref "U13") (pin "14") (pinfunction "Tblnk_14") (pintype "passive"))
    )
    (net (code "33") (name "Net-(U13-Tos)") (class "Default")
      (node (ref "R83") (pin "2") (pintype "passive"))
      (node (ref "U13") (pin "13") (pinfunction "Tos_13") (pintype "passive"))
    )
    (net (code "34") (name "Net-(U13-UVLO_Vsec)") (class "Default")
      (node (ref "R63") (pin "1") (pintype "passive"))
      (node (ref "R75") (pin "2") (pintype "passive"))
      (node (ref "U13") (pin "9") (pinfunction "UVLO_Vsec_9") (pintype "passive"))
    )
    (net (code "35") (name "Net-(U14-A)") (class "Default")
      (node (ref "C85") (pin "2") (pintype "passive"))
      (node (ref "R66") (pin "1") (pintype "passive"))
      (node (ref "U14") (pin "1") (pinfunction "A_1") (pintype "passive"))
    )
    (net (code "36") (name "Net-(U14-C)") (class "Default")
      (node (ref "C81") (pin "1") (pintype "passive"))
      (node (ref "R72") (pin "1") (pintype "passive"))
      (node (ref "U14") (pin "4") (pinfunction "C_4") (pintype "passive"))
    )
    (net (code "37") (name "Net-(U14-E)") (class "Default")
      (node (ref "C80") (pin "1") (pintype "passive"))
      (node (ref "R69") (pin "1") (pintype "passive"))
      (node (ref "U14") (pin "3") (pinfunction "E_3") (pintype "passive"))
      (node (ref "U15") (pin "1") (pinfunction "COLL_1") (pintype "passive"))
    )
    (net (code "38") (name "Net-(U14-K)") (class "Default")
      (node (ref "R74") (pin "2") (pintype "passive"))
      (node (ref "R76") (pin "2") (pintype "passive"))
      (node (ref "U14") (pin "2") (pinfunction "K_2") (pintype "passive"))
    )
    (net (code "39") (name "Net-(U15-REF)") (class "Default")
      (node (ref "C80") (pin "2") (pintype "passive"))
      (node (ref "C83") (pin "2") (pintype "passive"))
      (node (ref "R70") (pin "1") (pintype "passive"))
      (node (ref "R77") (pin "2") (pintype "passive"))
      (node (ref "U15") (pin "8") (pinfunction "REF_8") (pintype "passive"))
    )
    (net (code "40") (name "unconnected-(U13-NC-Pad2)") (class "Default")
      (node (ref "U13") (pin "2") (pinfunction "NC_2") (pintype "passive+no_connect"))
    )
    (net (code "41") (name "unconnected-(U13-NC-Pad15)") (class "Default")
      (node (ref "U13") (pin "15") (pinfunction "NC_15") (pintype "passive+no_connect"))
    )
    (net (code "42") (name "unconnected-(U13-NC-Pad16)") (class "Default")
      (node (ref "U13") (pin "16") (pinfunction "NC_16") (pintype "passive+no_connect"))
    )
    (net (code "43") (name "unconnected-(U13-NC-Pad34)") (class "Default")
      (node (ref "U13") (pin "34") (pinfunction "NC_34") (pintype "passive+no_connect"))
    )
    (net (code "44") (name "unconnected-(U13-NC-Pad37)") (class "Default")
      (node (ref "U13") (pin "37") (pinfunction "NC_37") (pintype "passive+no_connect"))
    )
    (net (code "45") (name "unconnected-(U13-SOUT-Pad30)") (class "Default")
      (node (ref "U13") (pin "30") (pinfunction "SOUT_30") (pintype "passive+no_connect"))
    )
    (net (code "46") (name "unconnected-(U13-TEST1-Pad1)") (class "Default")
      (node (ref "U13") (pin "1") (pinfunction "TEST1_1") (pintype "passive+no_connect"))
    )
    (net (code "47") (name "unconnected-(U13-TEST2-Pad36)") (class "Default")
      (node (ref "U13") (pin "36") (pinfunction "TEST2_36") (pintype "passive+no_connect"))
    )
    (net (code "48") (name "unconnected-(U15-COMP-Pad2)") (class "Default")
      (node (ref "U15") (pin "2") (pinfunction "COMP_2") (pintype "passive+no_connect"))
    )
    (net (code "49") (name "unconnected-(U15-Rmid-Pad7)") (class "Default")
      (node (ref "U15") (pin "7") (pinfunction "Rmid_7") (pintype "passive+no_connect"))
    )
    (net (code "50") (name "unconnected-(U15-Rtop-Pad4)") (class "Default")
      (node (ref "U15") (pin "4") (pinfunction "Rtop_4") (pintype "passive+no_connect"))
    )
  )
)
